# Adafruit_MAX9744.net
KiCad netlist of a schematic drawn in EAGLE
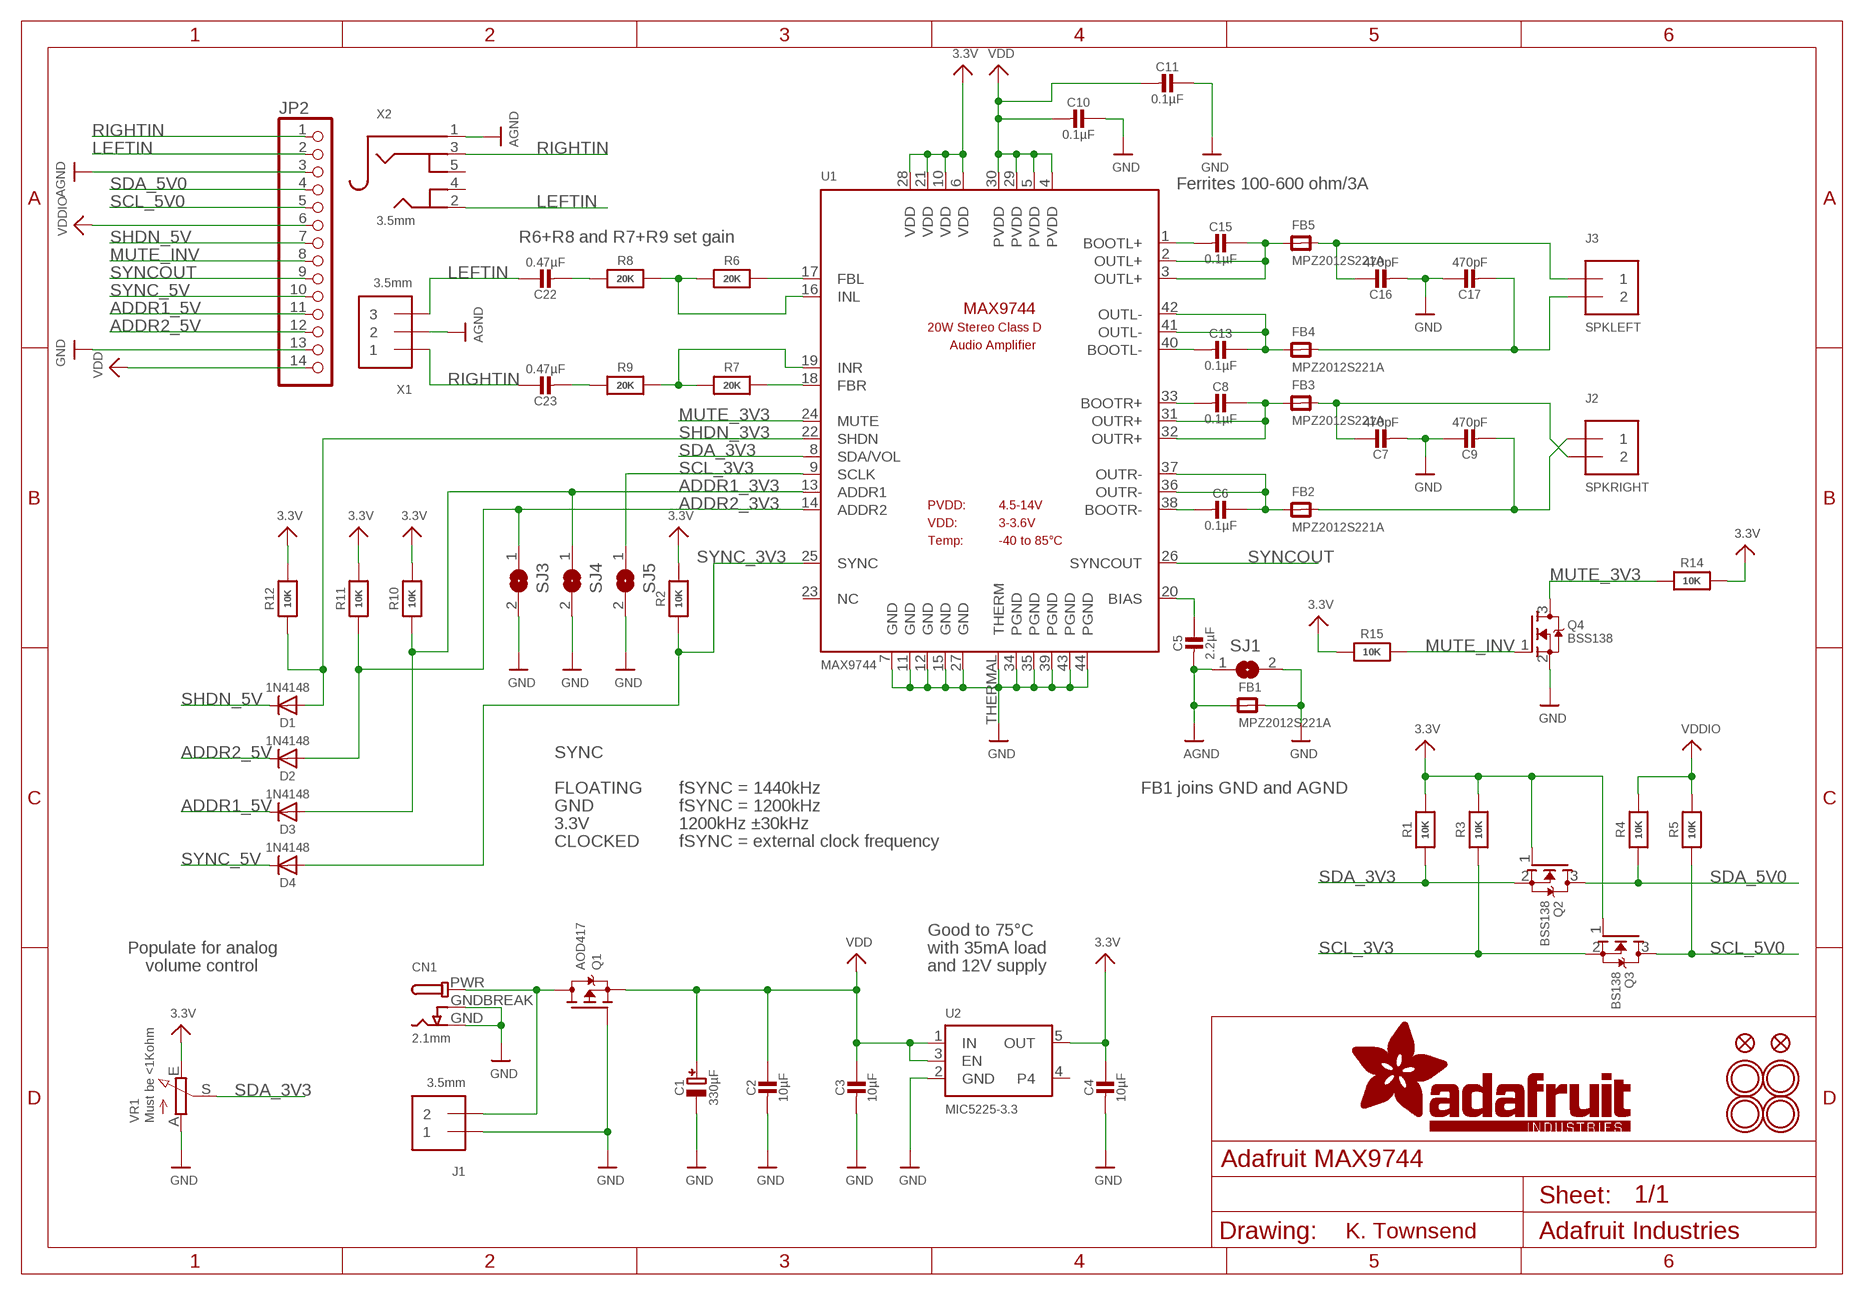
[diagram p0: schematic, sheet 1]

(export (version "E")
  (design (tool "Eeschema 10.0.6"))
  (components
    (comp (ref "C1")
      (value "330µF")
      (footprint "eagle-import:CELEC_3.5MM_8MM")
      (libsource (lib "eagle-import") (part "CAP_ELECTROLYTICPTH_3.5MMGRID_8MMDIA"))
    )
    (comp (ref "C2")
      (value "10µF")
      (footprint "eagle-import:0805-NO")
      (libsource (lib "eagle-import") (part "CAP_CERAMIC0805-NOOUTLINE"))
    )
    (comp (ref "C3")
      (value "10µF")
      (footprint "eagle-import:0805-NO")
      (libsource (lib "eagle-import") (part "CAP_CERAMIC0805-NOOUTLINE"))
    )
    (comp (ref "C4")
      (value "10µF")
      (footprint "eagle-import:0805-NO")
      (libsource (lib "eagle-import") (part "CAP_CERAMIC0805-NOOUTLINE"))
    )
    (comp (ref "C5")
      (value "2.2µF")
      (footprint "eagle-import:0805-NO")
      (libsource (lib "eagle-import") (part "CAP_CERAMIC0805-NOOUTLINE"))
    )
    (comp (ref "C6")
      (value "0.1µF")
      (footprint "eagle-import:0805-NO")
      (libsource (lib "eagle-import") (part "CAP_CERAMIC0805-NOOUTLINE"))
    )
    (comp (ref "C7")
      (value "470pF")
      (footprint "eagle-import:0805-NO")
      (libsource (lib "eagle-import") (part "CAP_CERAMIC0805-NOOUTLINE"))
    )
    (comp (ref "C8")
      (value "0.1µF")
      (footprint "eagle-import:0805-NO")
      (libsource (lib "eagle-import") (part "CAP_CERAMIC0805-NOOUTLINE"))
    )
    (comp (ref "C9")
      (value "470pF")
      (footprint "eagle-import:0805-NO")
      (libsource (lib "eagle-import") (part "CAP_CERAMIC0805-NOOUTLINE"))
    )
    (comp (ref "C10")
      (value "0.1µF")
      (footprint "eagle-import:0805-NO")
      (libsource (lib "eagle-import") (part "CAP_CERAMIC0805-NOOUTLINE"))
    )
    (comp (ref "C11")
      (value "0.1µF")
      (footprint "eagle-import:0805-NO")
      (libsource (lib "eagle-import") (part "CAP_CERAMIC0805-NOOUTLINE"))
    )
    (comp (ref "C13")
      (value "0.1µF")
      (footprint "eagle-import:0805-NO")
      (libsource (lib "eagle-import") (part "CAP_CERAMIC0805-NOOUTLINE"))
    )
    (comp (ref "C15")
      (value "0.1µF")
      (footprint "eagle-import:0805-NO")
      (libsource (lib "eagle-import") (part "CAP_CERAMIC0805-NOOUTLINE"))
    )
    (comp (ref "C16")
      (value "470pF")
      (footprint "eagle-import:0805-NO")
      (libsource (lib "eagle-import") (part "CAP_CERAMIC0805-NOOUTLINE"))
    )
    (comp (ref "C17")
      (value "470pF")
      (footprint "eagle-import:0805-NO")
      (libsource (lib "eagle-import") (part "CAP_CERAMIC0805-NOOUTLINE"))
    )
    (comp (ref "C22")
      (value "0.47µF")
      (footprint "eagle-import:0805-NO")
      (libsource (lib "eagle-import") (part "CAP_CERAMIC0805-NOOUTLINE"))
    )
    (comp (ref "C23")
      (value "0.47µF")
      (footprint "eagle-import:0805-NO")
      (libsource (lib "eagle-import") (part "CAP_CERAMIC0805-NOOUTLINE"))
    )
    (comp (ref "CN1")
      (value "2.1mm")
      (footprint "eagle-import:DCJACK_2MM_SMT")
      (libsource (lib "eagle-import") (part "DCBARRELSMT_CORRECT"))
    )
    (comp (ref "D1")
      (value "1N4148")
      (footprint "eagle-import:SOD-323")
      (libsource (lib "eagle-import") (part "DIODESOD-323"))
    )
    (comp (ref "D2")
      (value "1N4148")
      (footprint "eagle-import:SOD-323")
      (libsource (lib "eagle-import") (part "DIODESOD-323"))
    )
    (comp (ref "D3")
      (value "1N4148")
      (footprint "eagle-import:SOD-323")
      (libsource (lib "eagle-import") (part "DIODESOD-323"))
    )
    (comp (ref "D4")
      (value "1N4148")
      (footprint "eagle-import:SOD-323")
      (libsource (lib "eagle-import") (part "DIODESOD-323"))
    )
    (comp (ref "FB1")
      (value "MPZ2012S221A")
      (footprint "eagle-import:_0805")
      (libsource (lib "eagle-import") (part "FERRITE_0805"))
    )
    (comp (ref "FB2")
      (value "MPZ2012S221A")
      (footprint "eagle-import:_0805")
      (libsource (lib "eagle-import") (part "FERRITE_0805"))
    )
    (comp (ref "FB3")
      (value "MPZ2012S221A")
      (footprint "eagle-import:_0805")
      (libsource (lib "eagle-import") (part "FERRITE_0805"))
    )
    (comp (ref "FB4")
      (value "MPZ2012S221A")
      (footprint "eagle-import:_0805")
      (libsource (lib "eagle-import") (part "FERRITE_0805"))
    )
    (comp (ref "FB5")
      (value "MPZ2012S221A")
      (footprint "eagle-import:_0805")
      (libsource (lib "eagle-import") (part "FERRITE_0805"))
    )
    (comp (ref "FID1")
      (value "FIDUCIAL\"\"")
      (footprint "eagle-import:FIDUCIAL_1MM")
      (libsource (lib "eagle-import") (part "FIDUCIAL{dblquote}{dblquote}"))
    )
    (comp (ref "FID2")
      (value "FIDUCIAL\"\"")
      (footprint "eagle-import:FIDUCIAL_1MM")
      (libsource (lib "eagle-import") (part "FIDUCIAL{dblquote}{dblquote}"))
    )
    (comp (ref "J1")
      (value "3.5mm")
      (footprint "eagle-import:TERMBLOCK_1X2-3.5MM")
      (libsource (lib "eagle-import") (part "TERMBLOCK_1X2"))
    )
    (comp (ref "J2")
      (value "SPKRIGHT")
      (footprint "eagle-import:TERMBLOCK_1X2-3.5MM")
      (libsource (lib "eagle-import") (part "TERMBLOCK_1X2"))
    )
    (comp (ref "J3")
      (value "SPKLEFT")
      (footprint "eagle-import:TERMBLOCK_1X2-3.5MM")
      (libsource (lib "eagle-import") (part "TERMBLOCK_1X2"))
    )
    (comp (ref "JP2")
      (value "HEADER-1X14")
      (footprint "eagle-import:1X14_ROUND70")
      (libsource (lib "eagle-import") (part "HEADER-1X14"))
    )
    (comp (ref "Q1")
      (value "AOD417")
      (footprint "eagle-import:TO252")
      (libsource (lib "eagle-import") (part "MOSFET-PTO252"))
    )
    (comp (ref "Q2")
      (value "BSS138")
      (footprint "eagle-import:SOT23-WIDE")
      (libsource (lib "eagle-import") (part "MOSFET-NWIDE"))
    )
    (comp (ref "Q3")
      (value "BS138")
      (footprint "eagle-import:SOT23-WIDE")
      (libsource (lib "eagle-import") (part "MOSFET-NWIDE"))
    )
    (comp (ref "Q4")
      (value "BSS138")
      (footprint "eagle-import:SOT23-WIDE")
      (libsource (lib "eagle-import") (part "MOSFET-NWIDE"))
    )
    (comp (ref "R1")
      (value "10K")
      (footprint "eagle-import:0805-NO")
      (libsource (lib "eagle-import") (part "RESISTOR0805_NOOUTLINE"))
    )
    (comp (ref "R2")
      (value "10K")
      (footprint "eagle-import:_0805MP")
      (libsource (lib "eagle-import") (part "RESISTOR_0805MP"))
    )
    (comp (ref "R3")
      (value "10K")
      (footprint "eagle-import:0805-NO")
      (libsource (lib "eagle-import") (part "RESISTOR0805_NOOUTLINE"))
    )
    (comp (ref "R4")
      (value "10K")
      (footprint "eagle-import:0805-NO")
      (libsource (lib "eagle-import") (part "RESISTOR0805_NOOUTLINE"))
    )
    (comp (ref "R5")
      (value "10K")
      (footprint "eagle-import:0805-NO")
      (libsource (lib "eagle-import") (part "RESISTOR0805_NOOUTLINE"))
    )
    (comp (ref "R6")
      (value "20K")
      (footprint "eagle-import:0805-NO")
      (libsource (lib "eagle-import") (part "RESISTOR0805_NOOUTLINE"))
    )
    (comp (ref "R7")
      (value "20K")
      (footprint "eagle-import:0805-NO")
      (libsource (lib "eagle-import") (part "RESISTOR0805_NOOUTLINE"))
    )
    (comp (ref "R8")
      (value "20K")
      (footprint "eagle-import:0805-NO")
      (libsource (lib "eagle-import") (part "RESISTOR0805_NOOUTLINE"))
    )
    (comp (ref "R9")
      (value "20K")
      (footprint "eagle-import:0805-NO")
      (libsource (lib "eagle-import") (part "RESISTOR0805_NOOUTLINE"))
    )
    (comp (ref "R10")
      (value "10K")
      (footprint "eagle-import:_0805MP")
      (libsource (lib "eagle-import") (part "RESISTOR_0805MP"))
    )
    (comp (ref "R11")
      (value "10K")
      (footprint "eagle-import:_0805MP")
      (libsource (lib "eagle-import") (part "RESISTOR_0805MP"))
    )
    (comp (ref "R12")
      (value "10K")
      (footprint "eagle-import:0805-NO")
      (libsource (lib "eagle-import") (part "RESISTOR0805_NOOUTLINE"))
    )
    (comp (ref "R14")
      (value "10K")
      (footprint "eagle-import:_0805MP")
      (libsource (lib "eagle-import") (part "RESISTOR_0805MP"))
    )
    (comp (ref "R15")
      (value "10K")
      (footprint "eagle-import:_0805MP")
      (libsource (lib "eagle-import") (part "RESISTOR_0805MP"))
    )
    (comp (ref "SJ1")
      (value "SOLDERJUMPER")
      (footprint "eagle-import:SOLDERJUMPER_ARROW_NOPASTE")
      (fields (field (name "BOM") "EXCLUDE"))
      (libsource (lib "eagle-import") (part "SOLDERJUMPER"))
    )
    (comp (ref "SJ3")
      (value "SOLDERJUMPER")
      (footprint "eagle-import:SOLDERJUMPER_ARROW_NOPASTE")
      (libsource (lib "eagle-import") (part "SOLDERJUMPER"))
    )
    (comp (ref "SJ4")
      (value "SOLDERJUMPER")
      (footprint "eagle-import:SOLDERJUMPER_ARROW_NOPASTE")
      (libsource (lib "eagle-import") (part "SOLDERJUMPER"))
    )
    (comp (ref "SJ5")
      (value "SOLDERJUMPER")
      (footprint "eagle-import:SOLDERJUMPER_ARROW_NOPASTE")
      (libsource (lib "eagle-import") (part "SOLDERJUMPER"))
    )
    (comp (ref "U$29")
      (value "MOUNTINGHOLE2.5_THICK")
      (footprint "eagle-import:MOUNTINGHOLE_2.5_PLATED_THICK")
      (libsource (lib "eagle-import") (part "MOUNTINGHOLE2.5_THICK"))
    )
    (comp (ref "U$38")
      (value "MOUNTINGHOLE2.5_THICK")
      (footprint "eagle-import:MOUNTINGHOLE_2.5_PLATED_THICK")
      (libsource (lib "eagle-import") (part "MOUNTINGHOLE2.5_THICK"))
    )
    (comp (ref "U$39")
      (value "MOUNTINGHOLE2.5_THICK")
      (footprint "eagle-import:MOUNTINGHOLE_2.5_PLATED_THICK")
      (libsource (lib "eagle-import") (part "MOUNTINGHOLE2.5_THICK"))
    )
    (comp (ref "U$40")
      (value "MOUNTINGHOLE2.5_THICK")
      (footprint "eagle-import:MOUNTINGHOLE_2.5_PLATED_THICK")
      (libsource (lib "eagle-import") (part "MOUNTINGHOLE2.5_THICK"))
    )
    (comp (ref "U1")
      (value "MAX9744")
      (footprint "eagle-import:TQFN44_7MM")
      (libsource (lib "eagle-import") (part "AUDIOAMP_MAX9744"))
    )
    (comp (ref "U2")
      (value "MIC5225-3.3")
      (footprint "eagle-import:SOT23-5")
      (libsource (lib "eagle-import") (part "VREG_SOT23-5"))
    )
    (comp (ref "VR1")
      (value "Must be <1Kohm")
      (footprint "eagle-import:TRIMPOT_100MILPTH")
      (libsource (lib "eagle-import") (part "TRIMPOT100MIL"))
    )
    (comp (ref "X1")
      (value "3.5mm")
      (footprint "eagle-import:TERMBLOCK_1X3-3.5MM")
      (libsource (lib "eagle-import") (part "TERMBLOCK_1X3"))
    )
    (comp (ref "X2")
      (value "3.5mm")
      (footprint "eagle-import:4UCONN_19269")
      (libsource (lib "eagle-import") (part "AUDIO_3.5MMJACK"))
    )
  )
  (nets
    (net (code "1") (name "/ADDR1_3V3") (class "Default")
      (node (ref "D3") (pin "A") (pinfunction "A_A") (pintype "passive"))
      (node (ref "R10") (pin "1") (pinfunction "1_1") (pintype "passive"))
      (node (ref "SJ4") (pin "1") (pinfunction "1_1") (pintype "passive"))
      (node (ref "U1") (pin "13") (pinfunction "ADDR1_13") (pintype "input"))
    )
    (net (code "2") (name "/ADDR1_5V") (class "Default")
      (node (ref "D3") (pin "C") (pinfunction "C_C") (pintype "passive"))
      (node (ref "JP2") (pin "11") (pinfunction "11_11") (pintype "passive"))
    )
    (net (code "3") (name "/ADDR2_3V3") (class "Default")
      (node (ref "D2") (pin "A") (pinfunction "A_A") (pintype "passive"))
      (node (ref "R11") (pin "1") (pinfunction "1_1") (pintype "passive"))
      (node (ref "SJ3") (pin "1") (pinfunction "1_1") (pintype "passive"))
      (node (ref "U1") (pin "14") (pinfunction "ADDR2_14") (pintype "input"))
    )
    (net (code "4") (name "/ADDR2_5V") (class "Default")
      (node (ref "D2") (pin "C") (pinfunction "C_C") (pintype "passive"))
      (node (ref "JP2") (pin "12") (pinfunction "12_12") (pintype "passive"))
    )
    (net (code "5") (name "/LEFTIN") (class "Default")
      (node (ref "C22") (pin "1") (pinfunction "1_1") (pintype "passive"))
      (node (ref "JP2") (pin "2") (pinfunction "2_2") (pintype "passive"))
      (node (ref "X1") (pin "3") (pinfunction "3_3") (pintype "passive"))
      (node (ref "X2") (pin "2") (pinfunction "P$5_2") (pintype "bidirectional"))
    )
    (net (code "6") (name "/MUTE_3V3") (class "Default")
      (node (ref "Q4") (pin "3") (pinfunction "D_3") (pintype "bidirectional"))
      (node (ref "R14") (pin "1") (pinfunction "1_1") (pintype "passive"))
      (node (ref "U1") (pin "24") (pinfunction "MUTE_24") (pintype "input"))
    )
    (net (code "7") (name "/MUTE_INV") (class "Default")
      (node (ref "JP2") (pin "8") (pinfunction "8_8") (pintype "passive"))
      (node (ref "Q4") (pin "1") (pinfunction "G_1") (pintype "bidirectional"))
      (node (ref "R15") (pin "2") (pinfunction "2_2") (pintype "passive"))
    )
    (net (code "8") (name "/RIGHTIN") (class "Default")
      (node (ref "C23") (pin "1") (pinfunction "1_1") (pintype "passive"))
      (node (ref "JP2") (pin "1") (pinfunction "1_1") (pintype "passive"))
      (node (ref "X1") (pin "1") (pinfunction "1_1") (pintype "passive"))
      (node (ref "X2") (pin "3") (pinfunction "P$2_3") (pintype "bidirectional"))
    )
    (net (code "9") (name "/SCL_3V3") (class "Default")
      (node (ref "Q3") (pin "2") (pinfunction "S_2") (pintype "bidirectional"))
      (node (ref "R3") (pin "1") (pinfunction "1_1") (pintype "passive"))
      (node (ref "SJ5") (pin "1") (pinfunction "1_1") (pintype "passive"))
      (node (ref "U1") (pin "9") (pinfunction "SCLK_9") (pintype "bidirectional"))
    )
    (net (code "10") (name "/SCL_5V0") (class "Default")
      (node (ref "JP2") (pin "5") (pinfunction "5_5") (pintype "passive"))
      (node (ref "Q3") (pin "3") (pinfunction "D_3") (pintype "bidirectional"))
      (node (ref "R5") (pin "1") (pinfunction "1_1") (pintype "passive"))
    )
    (net (code "11") (name "/SDA_3V3") (class "Default")
      (node (ref "Q2") (pin "2") (pinfunction "S_2") (pintype "bidirectional"))
      (node (ref "R1") (pin "1") (pinfunction "1_1") (pintype "passive"))
      (node (ref "U1") (pin "8") (pinfunction "SDA/VOL_8") (pintype "bidirectional"))
      (node (ref "VR1") (pin "S") (pinfunction "S_S") (pintype "passive"))
    )
    (net (code "12") (name "/SDA_5V0") (class "Default")
      (node (ref "JP2") (pin "4") (pinfunction "4_4") (pintype "passive"))
      (node (ref "Q2") (pin "3") (pinfunction "D_3") (pintype "bidirectional"))
      (node (ref "R4") (pin "1") (pinfunction "1_1") (pintype "passive"))
    )
    (net (code "13") (name "/SHDN_3V3") (class "Default")
      (node (ref "D1") (pin "A") (pinfunction "A_A") (pintype "passive"))
      (node (ref "R12") (pin "1") (pinfunction "1_1") (pintype "passive"))
      (node (ref "U1") (pin "22") (pinfunction "SHDN_22") (pintype "input"))
    )
    (net (code "14") (name "/SHDN_5V") (class "Default")
      (node (ref "D1") (pin "C") (pinfunction "C_C") (pintype "passive"))
      (node (ref "JP2") (pin "7") (pinfunction "7_7") (pintype "passive"))
    )
    (net (code "15") (name "/SYNCOUT") (class "Default")
      (node (ref "JP2") (pin "9") (pinfunction "9_9") (pintype "passive"))
      (node (ref "U1") (pin "26") (pinfunction "SYNCOUT_26") (pintype "output"))
    )
    (net (code "16") (name "/SYNC_3V3") (class "Default")
      (node (ref "D4") (pin "A") (pinfunction "A_A") (pintype "passive"))
      (node (ref "R2") (pin "1") (pinfunction "1_1") (pintype "passive"))
      (node (ref "U1") (pin "25") (pinfunction "SYNC_25") (pintype "input"))
    )
    (net (code "17") (name "/SYNC_5V") (class "Default")
      (node (ref "D4") (pin "C") (pinfunction "C_C") (pintype "passive"))
      (node (ref "JP2") (pin "10") (pinfunction "10_10") (pintype "passive"))
    )
    (net (code "18") (name "3.3V") (class "Default")
      (node (ref "C4") (pin "1") (pinfunction "1_1") (pintype "passive"))
      (node (ref "Q2") (pin "1") (pinfunction "G_1") (pintype "bidirectional"))
      (node (ref "Q3") (pin "1") (pinfunction "G_1") (pintype "bidirectional"))
      (node (ref "R1") (pin "2") (pinfunction "2_2") (pintype "passive"))
      (node (ref "R10") (pin "2") (pinfunction "2_2") (pintype "passive"))
      (node (ref "R11") (pin "2") (pinfunction "2_2") (pintype "passive"))
      (node (ref "R12") (pin "2") (pinfunction "2_2") (pintype "passive"))
      (node (ref "R14") (pin "2") (pinfunction "2_2") (pintype "passive"))
      (node (ref "R15") (pin "1") (pinfunction "1_1") (pintype "passive"))
      (node (ref "R2") (pin "2") (pinfunction "2_2") (pintype "passive"))
      (node (ref "R3") (pin "2") (pinfunction "2_2") (pintype "passive"))
      (node (ref "U1") (pin "10") (pinfunction "VDD_10") (pintype "power_in"))
      (node (ref "U1") (pin "21") (pinfunction "VDD_21") (pintype "power_in"))
      (node (ref "U1") (pin "28") (pinfunction "VDD_28") (pintype "power_in"))
      (node (ref "U1") (pin "6") (pinfunction "VDD_6") (pintype "power_in"))
      (node (ref "U2") (pin "5") (pinfunction "OUT_5") (pintype "power_in"))
      (node (ref "VR1") (pin "E") (pinfunction "E_E") (pintype "passive"))
    )
    (net (code "19") (name "AGND") (class "Default")
      (node (ref "C5") (pin "2") (pinfunction "2_2") (pintype "passive"))
      (node (ref "FB1") (pin "1") (pinfunction "P$1_1") (pintype "passive"))
      (node (ref "JP2") (pin "3") (pinfunction "3_3") (pintype "passive"))
      (node (ref "SJ1") (pin "1") (pinfunction "1_1") (pintype "passive"))
      (node (ref "X1") (pin "2") (pinfunction "2_2") (pintype "passive"))
      (node (ref "X2") (pin "1") (pinfunction "P$1_1") (pintype "bidirectional"))
    )
    (net (code "20") (name "GND") (class "Default")
      (node (ref "C1") (pin "-") (pinfunction "-_-") (pintype "passive"))
      (node (ref "C10") (pin "1") (pinfunction "1_1") (pintype "passive"))
      (node (ref "C11") (pin "1") (pinfunction "1_1") (pintype "passive"))
      (node (ref "C16") (pin "2") (pinfunction "2_2") (pintype "passive"))
      (node (ref "C17") (pin "1") (pinfunction "1_1") (pintype "passive"))
      (node (ref "C2") (pin "2") (pinfunction "2_2") (pintype "passive"))
      (node (ref "C3") (pin "2") (pinfunction "2_2") (pintype "passive"))
      (node (ref "C4") (pin "2") (pinfunction "2_2") (pintype "passive"))
      (node (ref "C7") (pin "2") (pinfunction "2_2") (pintype "passive"))
      (node (ref "C9") (pin "1") (pinfunction "1_1") (pintype "passive"))
      (node (ref "CN1") (pin "GND") (pinfunction "GND_GND") (pintype "power_in"))
      (node (ref "CN1") (pin "GNDBREAK") (pinfunction "GNDBREAK_GNDBREAK") (pintype "power_in"))
      (node (ref "FB1") (pin "2") (pinfunction "P$2_2") (pintype "passive"))
      (node (ref "J1") (pin "1") (pinfunction "1_1") (pintype "passive"))
      (node (ref "JP2") (pin "13") (pinfunction "13_13") (pintype "passive"))
      (node (ref "Q1") (pin "1") (pinfunction "G_1") (pintype "passive"))
      (node (ref "Q4") (pin "2") (pinfunction "S_2") (pintype "bidirectional"))
      (node (ref "SJ1") (pin "2") (pinfunction "2_2") (pintype "passive"))
      (node (ref "SJ3") (pin "2") (pinfunction "2_2") (pintype "passive"))
      (node (ref "SJ4") (pin "2") (pinfunction "2_2") (pintype "passive"))
      (node (ref "SJ5") (pin "2") (pinfunction "2_2") (pintype "passive"))
      (node (ref "U1") (pin "11") (pinfunction "GND_11") (pintype "power_in"))
      (node (ref "U1") (pin "12") (pinfunction "GND_12") (pintype "power_in"))
      (node (ref "U1") (pin "15") (pinfunction "GND_15") (pintype "power_in"))
      (node (ref "U1") (pin "27") (pinfunction "GND_27") (pintype "power_in"))
      (node (ref "U1") (pin "34") (pinfunction "PGND_34") (pintype "power_in"))
      (node (ref "U1") (pin "35") (pinfunction "PGND_35") (pintype "power_in"))
      (node (ref "U1") (pin "39") (pinfunction "PGND_39") (pintype "power_in"))
      (node (ref "U1") (pin "43") (pinfunction "PGND_43") (pintype "power_in"))
      (node (ref "U1") (pin "44") (pinfunction "PGND_44") (pintype "power_in"))
      (node (ref "U1") (pin "7") (pinfunction "GND_7") (pintype "power_in"))
      (node (ref "U1") (pin "THERMAL") (pinfunction "THERM_THERMAL") (pintype "power_in"))
      (node (ref "U2") (pin "2") (pinfunction "GND_2") (pintype "power_in"))
      (node (ref "VR1") (pin "A") (pinfunction "A_A") (pintype "passive"))
    )
    (net (code "21") (name "Net-(C22-Pad2)") (class "Default")
      (node (ref "C22") (pin "2") (pinfunction "2_2") (pintype "passive"))
      (node (ref "R8") (pin "1") (pinfunction "1_1") (pintype "passive"))
    )
    (net (code "22") (name "Net-(C23-Pad2)") (class "Default")
      (node (ref "C23") (pin "2") (pinfunction "2_2") (pintype "passive"))
      (node (ref "R9") (pin "1") (pinfunction "1_1") (pintype "passive"))
    )
    (net (code "23") (name "Net-(FB2-P$1)") (class "Default")
      (node (ref "C6") (pin "1") (pinfunction "1_1") (pintype "passive"))
      (node (ref "FB2") (pin "1") (pinfunction "P$1_1") (pintype "passive"))
      (node (ref "U1") (pin "36") (pinfunction "OUTR-_36") (pintype "output"))
      (node (ref "U1") (pin "37") (pinfunction "OUTR-_37") (pintype "output"))
    )
    (net (code "24") (name "Net-(FB2-P$2)") (class "Default")
      (node (ref "C9") (pin "2") (pinfunction "2_2") (pintype "passive"))
      (node (ref "FB2") (pin "2") (pinfunction "P$2_2") (pintype "passive"))
      (node (ref "J2") (pin "1") (pinfunction "1_1") (pintype "passive"))
    )
    (net (code "25") (name "Net-(FB3-P$1)") (class "Default")
      (node (ref "C8") (pin "1") (pinfunction "1_1") (pintype "passive"))
      (node (ref "FB3") (pin "1") (pinfunction "P$1_1") (pintype "passive"))
      (node (ref "U1") (pin "31") (pinfunction "OUTR+_31") (pintype "output"))
      (node (ref "U1") (pin "32") (pinfunction "OUTR+_32") (pintype "output"))
    )
    (net (code "26") (name "Net-(FB3-P$2)") (class "Default")
      (node (ref "C7") (pin "1") (pinfunction "1_1") (pintype "passive"))
      (node (ref "FB3") (pin "2") (pinfunction "P$2_2") (pintype "passive"))
      (node (ref "J2") (pin "2") (pinfunction "2_2") (pintype "passive"))
    )
    (net (code "27") (name "Net-(FB4-P$1)") (class "Default")
      (node (ref "C13") (pin "1") (pinfunction "1_1") (pintype "passive"))
      (node (ref "FB4") (pin "1") (pinfunction "P$1_1") (pintype "passive"))
      (node (ref "U1") (pin "41") (pinfunction "OUTL-_41") (pintype "output"))
      (node (ref "U1") (pin "42") (pinfunction "OUTL-_42") (pintype "output"))
    )
    (net (code "28") (name "Net-(FB4-P$2)") (class "Default")
      (node (ref "C17") (pin "2") (pinfunction "2_2") (pintype "passive"))
      (node (ref "FB4") (pin "2") (pinfunction "P$2_2") (pintype "passive"))
      (node (ref "J3") (pin "2") (pinfunction "2_2") (pintype "passive"))
    )
    (net (code "29") (name "Net-(FB5-P$1)") (class "Default")
      (node (ref "C15") (pin "1") (pinfunction "1_1") (pintype "passive"))
      (node (ref "FB5") (pin "1") (pinfunction "P$1_1") (pintype "passive"))
      (node (ref "U1") (pin "2") (pinfunction "OUTL+_2") (pintype "output"))
      (node (ref "U1") (pin "3") (pinfunction "OUTL+_3") (pintype "output"))
    )
    (net (code "30") (name "Net-(FB5-P$2)") (class "Default")
      (node (ref "C16") (pin "1") (pinfunction "1_1") (pintype "passive"))
      (node (ref "FB5") (pin "2") (pinfunction "P$2_2") (pintype "passive"))
      (node (ref "J3") (pin "1") (pinfunction "1_1") (pintype "passive"))
    )
    (net (code "31") (name "Net-(Q1-D)") (class "Default")
      (node (ref "CN1") (pin "PWR") (pinfunction "PWR_PWR") (pintype "power_in"))
      (node (ref "J1") (pin "2") (pinfunction "2_2") (pintype "passive"))
      (node (ref "Q1") (pin "3") (pinfunction "D_3") (pintype "passive"))
    )
    (net (code "32") (name "Net-(U1-BIAS)") (class "Default")
      (node (ref "C5") (pin "1") (pinfunction "1_1") (pintype "passive"))
      (node (ref "U1") (pin "20") (pinfunction "BIAS_20") (pintype "bidirectional"))
    )
    (net (code "33") (name "Net-(U1-BOOTL+)") (class "Default")
      (node (ref "C15") (pin "2") (pinfunction "2_2") (pintype "passive"))
      (node (ref "U1") (pin "1") (pinfunction "BOOTL+_1") (pintype "bidirectional"))
    )
    (net (code "34") (name "Net-(U1-BOOTL-)") (class "Default")
      (node (ref "C13") (pin "2") (pinfunction "2_2") (pintype "passive"))
      (node (ref "U1") (pin "40") (pinfunction "BOOTL-_40") (pintype "bidirectional"))
    )
    (net (code "35") (name "Net-(U1-BOOTR+)") (class "Default")
      (node (ref "C8") (pin "2") (pinfunction "2_2") (pintype "passive"))
      (node (ref "U1") (pin "33") (pinfunction "BOOTR+_33") (pintype "bidirectional"))
    )
    (net (code "36") (name "Net-(U1-BOOTR-)") (class "Default")
      (node (ref "C6") (pin "2") (pinfunction "2_2") (pintype "passive"))
      (node (ref "U1") (pin "38") (pinfunction "BOOTR-_38") (pintype "bidirectional"))
    )
    (net (code "37") (name "Net-(U1-FBL)") (class "Default")
      (node (ref "R6") (pin "2") (pinfunction "2_2") (pintype "passive"))
      (node (ref "U1") (pin "17") (pinfunction "FBL_17") (pintype "bidirectional"))
    )
    (net (code "38") (name "Net-(U1-FBR)") (class "Default")
      (node (ref "R7") (pin "2") (pinfunction "2_2") (pintype "passive"))
      (node (ref "U1") (pin "18") (pinfunction "FBR_18") (pintype "bidirectional"))
    )
    (net (code "39") (name "Net-(U1-INL)") (class "Default")
      (node (ref "R6") (pin "1") (pinfunction "1_1") (pintype "passive"))
      (node (ref "R8") (pin "2") (pinfunction "2_2") (pintype "passive"))
      (node (ref "U1") (pin "16") (pinfunction "INL_16") (pintype "input"))
    )
    (net (code "40") (name "Net-(U1-INR)") (class "Default")
      (node (ref "R7") (pin "1") (pinfunction "1_1") (pintype "passive"))
      (node (ref "R9") (pin "2") (pinfunction "2_2") (pintype "passive"))
      (node (ref "U1") (pin "19") (pinfunction "INR_19") (pintype "input"))
    )
    (net (code "41") (name "VDD") (class "Default")
      (node (ref "C1") (pin "+") (pinfunction "+_+") (pintype "passive"))
      (node (ref "C10") (pin "2") (pinfunction "2_2") (pintype "passive"))
      (node (ref "C11") (pin "2") (pinfunction "2_2") (pintype "passive"))
      (node (ref "C2") (pin "1") (pinfunction "1_1") (pintype "passive"))
      (node (ref "C3") (pin "1") (pinfunction "1_1") (pintype "passive"))
      (node (ref "JP2") (pin "14") (pinfunction "14_14") (pintype "passive"))
      (node (ref "Q1") (pin "2") (pinfunction "S_2") (pintype "passive"))
      (node (ref "U1") (pin "29") (pinfunction "PVDD_29") (pintype "power_in"))
      (node (ref "U1") (pin "30") (pinfunction "PVDD_30") (pintype "power_in"))
      (node (ref "U1") (pin "4") (pinfunction "PVDD_4") (pintype "power_in"))
      (node (ref "U1") (pin "5") (pinfunction "PVDD_5") (pintype "power_in"))
      (node (ref "U2") (pin "1") (pinfunction "IN_1") (pintype "power_in"))
      (node (ref "U2") (pin "3") (pinfunction "EN_3") (pintype "input"))
    )
    (net (code "42") (name "VDDIO") (class "Default")
      (node (ref "JP2") (pin "6") (pinfunction "6_6") (pintype "passive"))
      (node (ref "R4") (pin "2") (pinfunction "2_2") (pintype "passive"))
      (node (ref "R5") (pin "2") (pinfunction "2_2") (pintype "passive"))
    )
    (net (code "43") (name "unconnected-(U1-NC-Pad23)") (class "Default")
      (node (ref "U1") (pin "23") (pinfunction "NC_23") (pintype "no_connect"))
    )
    (net (code "44") (name "unconnected-(U2-P4-Pad4)") (class "Default")
      (node (ref "U2") (pin "4") (pinfunction "P4_4") (pintype "bidirectional"))
    )
    (net (code "45") (name "unconnected-(X2-P$3-Pad5)") (class "Default")
      (node (ref "X2") (pin "5") (pinfunction "P$3_5") (pintype "bidirectional"))
    )
    (net (code "46") (name "unconnected-(X2-P$4-Pad4)") (class "Default")
      (node (ref "X2") (pin "4") (pinfunction "P$4_4") (pintype "bidirectional"))
    )
  )
)
